# scHnRk_6.net
KiCad netlist of a schematic drawn in EAGLE
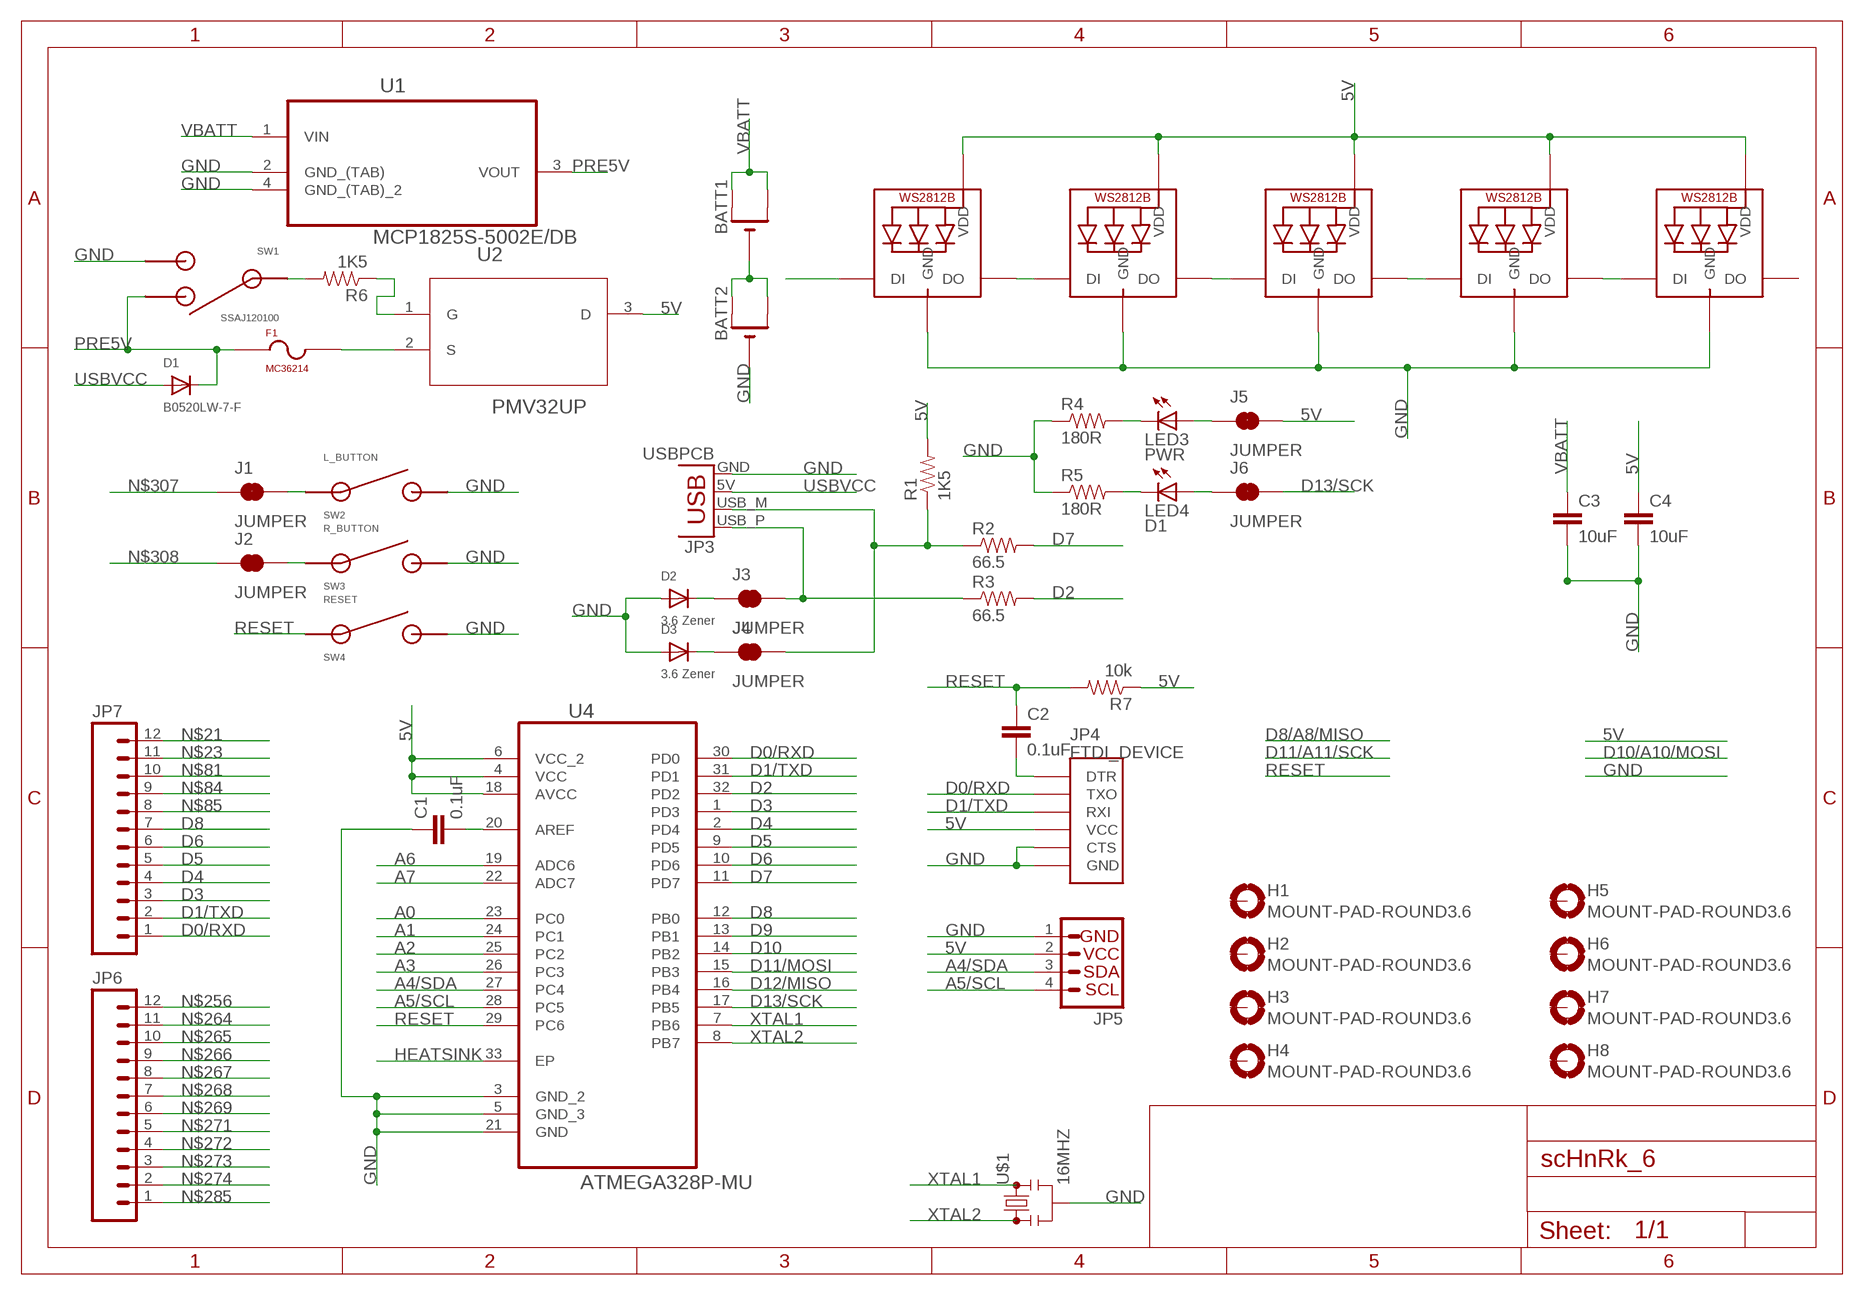
[diagram p0: schematic, sheet 1]

(export (version "E")
  (design (tool "Eeschema 10.0.6"))
  (components
    (comp (ref "BATT1")
      (value "CR2032SMT")
      (footprint "eagle-import:CR2032-SMD")
      (libsource (lib "eagle-import") (part "CR2032SMT"))
    )
    (comp (ref "BATT2")
      (value "CR2032SMT")
      (footprint "eagle-import:CR2032-SMD")
      (libsource (lib "eagle-import") (part "CR2032SMT"))
    )
    (comp (ref "C1")
      (value "0.1uF")
      (footprint "eagle-import:0805")
      (libsource (lib "eagle-import") (part "CAP0805"))
    )
    (comp (ref "C2")
      (value "0.1uF")
      (footprint "eagle-import:0805")
      (libsource (lib "eagle-import") (part "CAP0805"))
    )
    (comp (ref "C3")
      (value "10uF")
      (footprint "eagle-import:0805")
      (libsource (lib "eagle-import") (part "CAP0805"))
    )
    (comp (ref "C4")
      (value "10uF")
      (footprint "eagle-import:0805")
      (libsource (lib "eagle-import") (part "CAP0805"))
    )
    (comp (ref "D1")
      (value "B0520LW-7-F")
      (footprint "eagle-import:SOD-123")
      (libsource (lib "eagle-import") (part "DIODESOD-123"))
    )
    (comp (ref "D2")
      (value "3.6 Zener")
      (footprint "eagle-import:SOD-523")
      (libsource (lib "eagle-import") (part "DIODESOD-523"))
    )
    (comp (ref "D3")
      (value "3.6 Zener")
      (footprint "eagle-import:SOD-523")
      (libsource (lib "eagle-import") (part "DIODESOD-523"))
    )
    (comp (ref "F1")
      (value "MC36214")
      (footprint "eagle-import:MC36214")
      (libsource (lib "eagle-import") (part "MC36214"))
    )
    (comp (ref "H1")
      (value "MOUNT-PAD-ROUND3.6")
      (footprint "eagle-import:3,6-PAD")
      (libsource (lib "eagle-import") (part "MOUNT-PAD-ROUND3.6"))
    )
    (comp (ref "H2")
      (value "MOUNT-PAD-ROUND3.6")
      (footprint "eagle-import:3,6-PAD")
      (libsource (lib "eagle-import") (part "MOUNT-PAD-ROUND3.6"))
    )
    (comp (ref "H3")
      (value "MOUNT-PAD-ROUND3.6")
      (footprint "eagle-import:3,6-PAD")
      (libsource (lib "eagle-import") (part "MOUNT-PAD-ROUND3.6"))
    )
    (comp (ref "H4")
      (value "MOUNT-PAD-ROUND3.6")
      (footprint "eagle-import:3,6-PAD")
      (libsource (lib "eagle-import") (part "MOUNT-PAD-ROUND3.6"))
    )
    (comp (ref "H5")
      (value "MOUNT-PAD-ROUND3.6")
      (footprint "eagle-import:3,6-PAD")
      (libsource (lib "eagle-import") (part "MOUNT-PAD-ROUND3.6"))
    )
    (comp (ref "H6")
      (value "MOUNT-PAD-ROUND3.6")
      (footprint "eagle-import:3,6-PAD")
      (libsource (lib "eagle-import") (part "MOUNT-PAD-ROUND3.6"))
    )
    (comp (ref "H7")
      (value "MOUNT-PAD-ROUND3.6")
      (footprint "eagle-import:3,6-PAD")
      (libsource (lib "eagle-import") (part "MOUNT-PAD-ROUND3.6"))
    )
    (comp (ref "H8")
      (value "MOUNT-PAD-ROUND3.6")
      (footprint "eagle-import:3,6-PAD")
      (libsource (lib "eagle-import") (part "MOUNT-PAD-ROUND3.6"))
    )
    (comp (ref "J1")
      (value "JUMPER")
      (footprint "eagle-import:PAD-JUMPER-2-NC_BY_TRACE_YES_SILK")
      (libsource (lib "eagle-import") (part "JUMPER-PAD-2-NC_BY_TRACE"))
    )
    (comp (ref "J2")
      (value "JUMPER")
      (footprint "eagle-import:PAD-JUMPER-2-NC_BY_TRACE_YES_SILK")
      (libsource (lib "eagle-import") (part "JUMPER-PAD-2-NC_BY_TRACE"))
    )
    (comp (ref "J3")
      (value "JUMPER")
      (footprint "eagle-import:PAD-JUMPER-2-NC_BY_TRACE_YES_SILK")
      (libsource (lib "eagle-import") (part "JUMPER-PAD-2-NC_BY_TRACE"))
    )
    (comp (ref "J4")
      (value "JUMPER")
      (footprint "eagle-import:PAD-JUMPER-2-NC_BY_TRACE_YES_SILK")
      (libsource (lib "eagle-import") (part "JUMPER-PAD-2-NC_BY_TRACE"))
    )
    (comp (ref "J5")
      (value "JUMPER")
      (footprint "eagle-import:PAD-JUMPER-2-NC_BY_TRACE_YES_SILK")
      (libsource (lib "eagle-import") (part "JUMPER-PAD-2-NC_BY_TRACE"))
    )
    (comp (ref "J6")
      (value "JUMPER")
      (footprint "eagle-import:PAD-JUMPER-2-NC_BY_TRACE_YES_SILK")
      (libsource (lib "eagle-import") (part "JUMPER-PAD-2-NC_BY_TRACE"))
    )
    (comp (ref "JP3")
      (value "USBPCB")
      (footprint "eagle-import:USB-A-PCB")
      (libsource (lib "eagle-import") (part "USBPCB"))
    )
    (comp (ref "JP4")
      (value "FTDI_DEVICE")
      (footprint "eagle-import:FTDI_DEVICE_SIDE")
      (libsource (lib "eagle-import") (part "FTDI_DEVICE"))
    )
    (comp (ref "JP5")
      (value "I2C_STANDARD")
      (footprint "eagle-import:1X04")
      (libsource (lib "eagle-import") (part "I2C_STANDARD"))
    )
    (comp (ref "JP6")
      (value "M12PTH")
      (footprint "eagle-import:1X12")
      (libsource (lib "eagle-import") (part "M12PTH"))
    )
    (comp (ref "JP7")
      (value "M12PTH")
      (footprint "eagle-import:1X12")
      (libsource (lib "eagle-import") (part "M12PTH"))
    )
    (comp (ref "LED1")
      (value "WS2812B5050")
      (footprint "eagle-import:WS2812B")
      (libsource (lib "eagle-import") (part "WS2812B5050"))
    )
    (comp (ref "LED2")
      (value "WS2812B5050")
      (footprint "eagle-import:WS2812B")
      (libsource (lib "eagle-import") (part "WS2812B5050"))
    )
    (comp (ref "LED3")
      (value "PWR")
      (footprint "eagle-import:CHIPLED_0603")
      (libsource (lib "eagle-import") (part "LEDCHIPLED_0603"))
    )
    (comp (ref "LED4")
      (value "D1")
      (footprint "eagle-import:CHIPLED_0603")
      (libsource (lib "eagle-import") (part "LEDCHIPLED_0603"))
    )
    (comp (ref "LED5")
      (value "WS2812B5050")
      (footprint "eagle-import:WS2812B")
      (libsource (lib "eagle-import") (part "WS2812B5050"))
    )
    (comp (ref "LED6")
      (value "WS2812B5050")
      (footprint "eagle-import:WS2812B")
      (libsource (lib "eagle-import") (part "WS2812B5050"))
    )
    (comp (ref "LED7")
      (value "WS2812B5050")
      (footprint "eagle-import:WS2812B")
      (libsource (lib "eagle-import") (part "WS2812B5050"))
    )
    (comp (ref "R1")
      (value "1K5")
      (footprint "eagle-import:0805")
      (libsource (lib "eagle-import") (part "RESISTOR0805-RES"))
    )
    (comp (ref "R2")
      (value "66.5")
      (footprint "eagle-import:0603-RES")
      (libsource (lib "eagle-import") (part "RESISTOR0603-RES"))
    )
    (comp (ref "R3")
      (value "66.5")
      (footprint "eagle-import:0603-RES")
      (libsource (lib "eagle-import") (part "RESISTOR0603-RES"))
    )
    (comp (ref "R4")
      (value "180R")
      (footprint "eagle-import:0805")
      (libsource (lib "eagle-import") (part "RESISTOR0805-RES"))
    )
    (comp (ref "R5")
      (value "180R")
      (footprint "eagle-import:0805")
      (libsource (lib "eagle-import") (part "RESISTOR0805-RES"))
    )
    (comp (ref "R6")
      (value "1K5")
      (footprint "eagle-import:0805")
      (libsource (lib "eagle-import") (part "RESISTOR0805-RES"))
    )
    (comp (ref "R7")
      (value "10k")
      (footprint "eagle-import:0805")
      (libsource (lib "eagle-import") (part "RESISTOR0805-RES"))
    )
    (comp (ref "SW1")
      (value "SSAJ120100")
      (footprint "eagle-import:SSAJ120100")
      (libsource (lib "eagle-import") (part "SSAJ120100"))
    )
    (comp (ref "SW2")
      (value "L_BUTTON")
      (footprint "eagle-import:SKRBAGE010")
      (libsource (lib "eagle-import") (part "SKRBAGE010"))
    )
    (comp (ref "SW3")
      (value "R_BUTTON")
      (footprint "eagle-import:SKRBAGE010")
      (libsource (lib "eagle-import") (part "SKRBAGE010"))
    )
    (comp (ref "SW4")
      (value "RESET")
      (footprint "eagle-import:SKRBAGE010")
      (libsource (lib "eagle-import") (part "SKRBAGE010"))
    )
    (comp (ref "U$1")
      (value "16MHZ")
      (footprint "eagle-import:RESONATOR-SMD")
      (libsource (lib "eagle-import") (part "RESONATOR16MHZ"))
    )
    (comp (ref "U1")
      (value "MCP1825S-5002E/DB")
      (footprint "eagle-import:SOT230P700X180-4N")
      (libsource (lib "eagle-import") (part "MCP1825S-5002E/DB"))
    )
    (comp (ref "U2")
      (value "PMV32UP")
      (footprint "eagle-import:SOT95P230X110-3N")
      (libsource (lib "eagle-import") (part "PMV32UP"))
    )
    (comp (ref "U4")
      (value "ATMEGA328P-MU")
      (footprint "eagle-import:QFN50P500X500X100-33N")
      (libsource (lib "eagle-import") (part "ATMEGA328P-MU"))
    )
  )
  (nets
    (net (code "1") (name "/5V") (class "Default")
      (node (ref "C4") (pin "1") (pinfunction "1_1") (pintype "passive"))
      (node (ref "J5") (pin "2") (pinfunction "2_2") (pintype "passive"))
      (node (ref "JP4") (pin "P$4") (pinfunction "VCC_P$4") (pintype "bidirectional"))
      (node (ref "JP5") (pin "2") (pinfunction "2_2") (pintype "passive"))
      (node (ref "LED1") (pin "1-VDD") (pinfunction "VDD_1-VDD") (pintype "power_in"))
      (node (ref "LED2") (pin "1-VDD") (pinfunction "VDD_1-VDD") (pintype "power_in"))
      (node (ref "LED5") (pin "1-VDD") (pinfunction "VDD_1-VDD") (pintype "power_in"))
      (node (ref "LED6") (pin "1-VDD") (pinfunction "VDD_1-VDD") (pintype "power_in"))
      (node (ref "LED7") (pin "1-VDD") (pinfunction "VDD_1-VDD") (pintype "power_in"))
      (node (ref "R1") (pin "2") (pinfunction "2_2") (pintype "passive"))
      (node (ref "R7") (pin "1") (pinfunction "1_1") (pintype "passive"))
      (node (ref "U2") (pin "3") (pinfunction "D_3") (pintype "passive"))
      (node (ref "U4") (pin "18") (pinfunction "AVCC_18") (pintype "power_in"))
      (node (ref "U4") (pin "4") (pinfunction "VCC_4") (pintype "power_in"))
      (node (ref "U4") (pin "6") (pinfunction "VCC_2_6") (pintype "power_in"))
    )
    (net (code "2") (name "/A0") (class "Default")
      (node (ref "U4") (pin "23") (pinfunction "PC0_23") (pintype "bidirectional"))
    )
    (net (code "3") (name "/A1") (class "Default")
      (node (ref "U4") (pin "24") (pinfunction "PC1_24") (pintype "bidirectional"))
    )
    (net (code "4") (name "/A2") (class "Default")
      (node (ref "U4") (pin "25") (pinfunction "PC2_25") (pintype "bidirectional"))
    )
    (net (code "5") (name "/A3") (class "Default")
      (node (ref "U4") (pin "26") (pinfunction "PC3_26") (pintype "bidirectional"))
    )
    (net (code "6") (name "/A4{slash}SDA") (class "Default")
      (node (ref "JP5") (pin "3") (pinfunction "3_3") (pintype "passive"))
      (node (ref "U4") (pin "27") (pinfunction "PC4_27") (pintype "bidirectional"))
    )
    (net (code "7") (name "/A5{slash}SCL") (class "Default")
      (node (ref "JP5") (pin "4") (pinfunction "4_4") (pintype "passive"))
      (node (ref "U4") (pin "28") (pinfunction "PC5_28") (pintype "bidirectional"))
    )
    (net (code "8") (name "/A6") (class "Default")
      (node (ref "U4") (pin "19") (pinfunction "ADC6_19") (pintype "input"))
    )
    (net (code "9") (name "/A7") (class "Default")
      (node (ref "U4") (pin "22") (pinfunction "ADC7_22") (pintype "input"))
    )
    (net (code "10") (name "/D0{slash}RXD") (class "Default")
      (node (ref "JP4") (pin "P$2") (pinfunction "TXO_P$2") (pintype "bidirectional"))
      (node (ref "JP7") (pin "1") (pinfunction "1_1") (pintype "passive"))
      (node (ref "U4") (pin "30") (pinfunction "PD0_30") (pintype "bidirectional"))
    )
    (net (code "11") (name "/D1{slash}TXD") (class "Default")
      (node (ref "JP4") (pin "P$3") (pinfunction "RXI_P$3") (pintype "bidirectional"))
      (node (ref "JP7") (pin "2") (pinfunction "2_2") (pintype "passive"))
      (node (ref "U4") (pin "31") (pinfunction "PD1_31") (pintype "bidirectional"))
    )
    (net (code "12") (name "/D2") (class "Default")
      (node (ref "R3") (pin "2") (pinfunction "2_2") (pintype "passive"))
      (node (ref "U4") (pin "32") (pinfunction "PD2_32") (pintype "bidirectional"))
    )
    (net (code "13") (name "/D3") (class "Default")
      (node (ref "JP7") (pin "3") (pinfunction "3_3") (pintype "passive"))
      (node (ref "U4") (pin "1") (pinfunction "PD3_1") (pintype "bidirectional"))
    )
    (net (code "14") (name "/D4") (class "Default")
      (node (ref "JP7") (pin "4") (pinfunction "4_4") (pintype "passive"))
      (node (ref "U4") (pin "2") (pinfunction "PD4_2") (pintype "bidirectional"))
    )
    (net (code "15") (name "/D5") (class "Default")
      (node (ref "JP7") (pin "5") (pinfunction "5_5") (pintype "passive"))
      (node (ref "U4") (pin "9") (pinfunction "PD5_9") (pintype "bidirectional"))
    )
    (net (code "16") (name "/D6") (class "Default")
      (node (ref "JP7") (pin "6") (pinfunction "6_6") (pintype "passive"))
      (node (ref "U4") (pin "10") (pinfunction "PD6_10") (pintype "bidirectional"))
    )
    (net (code "17") (name "/D7") (class "Default")
      (node (ref "R2") (pin "2") (pinfunction "2_2") (pintype "passive"))
      (node (ref "U4") (pin "11") (pinfunction "PD7_11") (pintype "bidirectional"))
    )
    (net (code "18") (name "/D8") (class "Default")
      (node (ref "JP7") (pin "7") (pinfunction "7_7") (pintype "passive"))
      (node (ref "U4") (pin "12") (pinfunction "PB0_12") (pintype "bidirectional"))
    )
    (net (code "20") (name "/D9") (class "Default")
      (node (ref "U4") (pin "13") (pinfunction "PB1_13") (pintype "bidirectional"))
    )
    (net (code "21") (name "/D10") (class "Default")
      (node (ref "U4") (pin "14") (pinfunction "PB2_14") (pintype "bidirectional"))
    )
    (net (code "24") (name "/D11{slash}MOSI") (class "Default")
      (node (ref "U4") (pin "15") (pinfunction "PB3_15") (pintype "bidirectional"))
    )
    (net (code "25") (name "/D12{slash}MISO") (class "Default")
      (node (ref "U4") (pin "16") (pinfunction "PB4_16") (pintype "bidirectional"))
    )
    (net (code "26") (name "/D13{slash}SCK") (class "Default")
      (node (ref "J6") (pin "2") (pinfunction "2_2") (pintype "passive"))
      (node (ref "U4") (pin "17") (pinfunction "PB5_17") (pintype "bidirectional"))
    )
    (net (code "27") (name "/GND") (class "Default")
      (node (ref "BATT2") (pin "-") (pinfunction "-_-") (pintype "passive"))
      (node (ref "C1") (pin "1") (pinfunction "1_1") (pintype "passive"))
      (node (ref "C3") (pin "2") (pinfunction "2_2") (pintype "passive"))
      (node (ref "C4") (pin "2") (pinfunction "2_2") (pintype "passive"))
      (node (ref "D2") (pin "A") (pinfunction "A_A") (pintype "passive"))
      (node (ref "D3") (pin "A") (pinfunction "A_A") (pintype "passive"))
      (node (ref "JP3") (pin "GND") (pinfunction "GND_GND") (pintype "bidirectional"))
      (node (ref "JP4") (pin "P$5") (pinfunction "CTS_P$5") (pintype "bidirectional"))
      (node (ref "JP4") (pin "P$6") (pinfunction "GND_P$6") (pintype "bidirectional"))
      (node (ref "JP5") (pin "1") (pinfunction "1_1") (pintype "passive"))
      (node (ref "LED1") (pin "3-GND") (pinfunction "GND_3-GND") (pintype "power_in"))
      (node (ref "LED2") (pin "3-GND") (pinfunction "GND_3-GND") (pintype "power_in"))
      (node (ref "LED5") (pin "3-GND") (pinfunction "GND_3-GND") (pintype "power_in"))
      (node (ref "LED6") (pin "3-GND") (pinfunction "GND_3-GND") (pintype "power_in"))
      (node (ref "LED7") (pin "3-GND") (pinfunction "GND_3-GND") (pintype "power_in"))
      (node (ref "R4") (pin "1") (pinfunction "1_1") (pintype "passive"))
      (node (ref "R5") (pin "1") (pinfunction "1_1") (pintype "passive"))
      (node (ref "SW1") (pin "P$2") (pinfunction "P$2_P$2") (pintype "bidirectional"))
      (node (ref "SW2") (pin "P$2") (pinfunction "P$2_P$2") (pintype "bidirectional"))
      (node (ref "SW2") (pin "P$4") (pinfunction "P$2_P$4") (pintype "bidirectional"))
      (node (ref "SW3") (pin "P$2") (pinfunction "P$2_P$2") (pintype "bidirectional"))
      (node (ref "SW3") (pin "P$4") (pinfunction "P$2_P$4") (pintype "bidirectional"))
      (node (ref "SW4") (pin "P$2") (pinfunction "P$2_P$2") (pintype "bidirectional"))
      (node (ref "SW4") (pin "P$4") (pinfunction "P$2_P$4") (pintype "bidirectional"))
      (node (ref "U$1") (pin "2") (pinfunction "2_2") (pintype "passive"))
      (node (ref "U1") (pin "2") (pinfunction "GND_(TAB)_2") (pintype "passive"))
      (node (ref "U1") (pin "4") (pinfunction "GND_(TAB)_2_4") (pintype "passive"))
      (node (ref "U4") (pin "21") (pinfunction "GND_21") (pintype "passive"))
      (node (ref "U4") (pin "3") (pinfunction "GND_2_3") (pintype "passive"))
      (node (ref "U4") (pin "5") (pinfunction "GND_3_5") (pintype "passive"))
    )
    (net (code "28") (name "/HEATSINK") (class "Default")
      (node (ref "U4") (pin "33") (pinfunction "EP_33") (pintype "passive"))
    )
    (net (code "29") (name "/N$21") (class "Default")
      (node (ref "JP7") (pin "12") (pinfunction "12_12") (pintype "passive"))
    )
    (net (code "30") (name "/N$23") (class "Default")
      (node (ref "JP7") (pin "11") (pinfunction "11_11") (pintype "passive"))
    )
    (net (code "31") (name "/N$81") (class "Default")
      (node (ref "JP7") (pin "10") (pinfunction "10_10") (pintype "passive"))
    )
    (net (code "32") (name "/N$84") (class "Default")
      (node (ref "JP7") (pin "9") (pinfunction "9_9") (pintype "passive"))
    )
    (net (code "33") (name "/N$85") (class "Default")
      (node (ref "JP7") (pin "8") (pinfunction "8_8") (pintype "passive"))
    )
    (net (code "34") (name "/N$256") (class "Default")
      (node (ref "JP6") (pin "12") (pinfunction "12_12") (pintype "passive"))
    )
    (net (code "35") (name "/N$264") (class "Default")
      (node (ref "JP6") (pin "11") (pinfunction "11_11") (pintype "passive"))
    )
    (net (code "36") (name "/N$265") (class "Default")
      (node (ref "JP6") (pin "10") (pinfunction "10_10") (pintype "passive"))
    )
    (net (code "37") (name "/N$266") (class "Default")
      (node (ref "JP6") (pin "9") (pinfunction "9_9") (pintype "passive"))
    )
    (net (code "38") (name "/N$267") (class "Default")
      (node (ref "JP6") (pin "8") (pinfunction "8_8") (pintype "passive"))
    )
    (net (code "39") (name "/N$268") (class "Default")
      (node (ref "JP6") (pin "7") (pinfunction "7_7") (pintype "passive"))
    )
    (net (code "40") (name "/N$269") (class "Default")
      (node (ref "JP6") (pin "6") (pinfunction "6_6") (pintype "passive"))
    )
    (net (code "41") (name "/N$271") (class "Default")
      (node (ref "JP6") (pin "5") (pinfunction "5_5") (pintype "passive"))
    )
    (net (code "42") (name "/N$272") (class "Default")
      (node (ref "JP6") (pin "4") (pinfunction "4_4") (pintype "passive"))
    )
    (net (code "43") (name "/N$273") (class "Default")
      (node (ref "JP6") (pin "3") (pinfunction "3_3") (pintype "passive"))
    )
    (net (code "44") (name "/N$274") (class "Default")
      (node (ref "JP6") (pin "2") (pinfunction "2_2") (pintype "passive"))
    )
    (net (code "45") (name "/N$285") (class "Default")
      (node (ref "JP6") (pin "1") (pinfunction "1_1") (pintype "passive"))
    )
    (net (code "46") (name "/N$307") (class "Default")
      (node (ref "J1") (pin "1") (pinfunction "1_1") (pintype "passive"))
    )
    (net (code "47") (name "/N$308") (class "Default")
      (node (ref "J2") (pin "1") (pinfunction "1_1") (pintype "passive"))
    )
    (net (code "48") (name "/PRE5V") (class "Default")
      (node (ref "D1") (pin "C") (pinfunction "C_C") (pintype "passive"))
      (node (ref "F1") (pin "P$1") (pinfunction "P$1_P$1") (pintype "bidirectional"))
      (node (ref "SW1") (pin "P$1") (pinfunction "P$1_P$1") (pintype "bidirectional"))
      (node (ref "U1") (pin "3") (pinfunction "VOUT_3") (pintype "output"))
    )
    (net (code "49") (name "/RESET") (class "Default")
      (node (ref "C2") (pin "1") (pinfunction "1_1") (pintype "passive"))
      (node (ref "R7") (pin "2") (pinfunction "2_2") (pintype "passive"))
      (node (ref "SW4") (pin "P$1") (pinfunction "P$1_P$1") (pintype "bidirectional"))
      (node (ref "SW4") (pin "P$3") (pinfunction "P$1_P$3") (pintype "bidirectional"))
      (node (ref "U4") (pin "29") (pinfunction "PC6_29") (pintype "bidirectional"))
    )
    (net (code "50") (name "/USBVCC") (class "Default")
      (node (ref "D1") (pin "A") (pinfunction "A_A") (pintype "passive"))
      (node (ref "JP3") (pin "5V") (pinfunction "VBUS_5V") (pintype "bidirectional"))
    )
    (net (code "51") (name "/VBATT") (class "Default")
      (node (ref "BATT1") (pin "+$1") (pinfunction "+_+$1") (pintype "passive"))
      (node (ref "BATT1") (pin "+$2") (pinfunction "+1_+$2") (pintype "passive"))
      (node (ref "C3") (pin "1") (pinfunction "1_1") (pintype "passive"))
      (node (ref "U1") (pin "1") (pinfunction "VIN_1") (pintype "input"))
    )
    (net (code "52") (name "/XTAL1") (class "Default")
      (node (ref "U$1") (pin "3") (pinfunction "3_3") (pintype "passive"))
      (node (ref "U4") (pin "7") (pinfunction "PB6_7") (pintype "bidirectional"))
    )
    (net (code "53") (name "/XTAL2") (class "Default")
      (node (ref "U$1") (pin "1") (pinfunction "1_1") (pintype "passive"))
      (node (ref "U4") (pin "8") (pinfunction "PB7_8") (pintype "bidirectional"))
    )
    (net (code "54") (name "Net-(BATT2-+)") (class "Default")
      (node (ref "BATT1") (pin "-") (pinfunction "-_-") (pintype "passive"))
      (node (ref "BATT2") (pin "+$1") (pinfunction "+_+$1") (pintype "passive"))
      (node (ref "BATT2") (pin "+$2") (pinfunction "+1_+$2") (pintype "passive"))
    )
    (net (code "55") (name "Net-(D2-C)") (class "Default")
      (node (ref "D2") (pin "K") (pinfunction "C_K") (pintype "passive"))
      (node (ref "J3") (pin "1") (pinfunction "1_1") (pintype "passive"))
    )
    (net (code "56") (name "Net-(D3-C)") (class "Default")
      (node (ref "D3") (pin "K") (pinfunction "C_K") (pintype "passive"))
      (node (ref "J4") (pin "1") (pinfunction "1_1") (pintype "passive"))
    )
    (net (code "57") (name "Net-(J1-Pad2)") (class "Default")
      (node (ref "J1") (pin "2") (pinfunction "2_2") (pintype "passive"))
      (node (ref "SW2") (pin "P$1") (pinfunction "P$1_P$1") (pintype "bidirectional"))
      (node (ref "SW2") (pin "P$3") (pinfunction "P$1_P$3") (pintype "bidirectional"))
    )
    (net (code "58") (name "Net-(J2-Pad2)") (class "Default")
      (node (ref "J2") (pin "2") (pinfunction "2_2") (pintype "passive"))
      (node (ref "SW3") (pin "P$1") (pinfunction "P$1_P$1") (pintype "bidirectional"))
      (node (ref "SW3") (pin "P$3") (pinfunction "P$1_P$3") (pintype "bidirectional"))
    )
    (net (code "59") (name "Net-(J5-Pad1)") (class "Default")
      (node (ref "J5") (pin "1") (pinfunction "1_1") (pintype "passive"))
      (node (ref "LED3") (pin "A") (pinfunction "A_A") (pintype "passive"))
    )
    (net (code "60") (name "Net-(J6-Pad1)") (class "Default")
      (node (ref "J6") (pin "1") (pinfunction "1_1") (pintype "passive"))
      (node (ref "LED4") (pin "A") (pinfunction "A_A") (pintype "passive"))
    )
    (net (code "61") (name "Net-(JP3-D+)") (class "Default")
      (node (ref "J3") (pin "2") (pinfunction "2_2") (pintype "passive"))
      (node (ref "JP3") (pin "USB_P") (pinfunction "D+_USB_P") (pintype "bidirectional"))
      (node (ref "R3") (pin "1") (pinfunction "1_1") (pintype "passive"))
    )
    (net (code "62") (name "Net-(JP3-D-)") (class "Default")
      (node (ref "J4") (pin "2") (pinfunction "2_2") (pintype "passive"))
      (node (ref "JP3") (pin "USB_M") (pinfunction "D-_USB_M") (pintype "bidirectional"))
      (node (ref "R1") (pin "1") (pinfunction "1_1") (pintype "passive"))
      (node (ref "R2") (pin "1") (pinfunction "1_1") (pintype "passive"))
    )
    (net (code "63") (name "Net-(JP4-DTR)") (class "Default")
      (node (ref "C2") (pin "2") (pinfunction "2_2") (pintype "passive"))
      (node (ref "JP4") (pin "P$1") (pinfunction "DTR_P$1") (pintype "bidirectional"))
    )
    (net (code "64") (name "Net-(LED1-DO)") (class "Default")
      (node (ref "LED1") (pin "2-DOUT") (pinfunction "DO_2-DOUT") (pintype "output"))
      (node (ref "LED2") (pin "4-DIN") (pinfunction "DI_4-DIN") (pintype "input"))
    )
    (net (code "65") (name "Net-(LED2-DO)") (class "Default")
      (node (ref "LED2") (pin "2-DOUT") (pinfunction "DO_2-DOUT") (pintype "output"))
      (node (ref "LED5") (pin "4-DIN") (pinfunction "DI_4-DIN") (pintype "input"))
    )
    (net (code "66") (name "Net-(LED3-PadC)") (class "Default")
      (node (ref "LED3") (pin "C") (pinfunction "C_C") (pintype "passive"))
      (node (ref "R4") (pin "2") (pinfunction "2_2") (pintype "passive"))
    )
    (net (code "67") (name "Net-(LED4-PadC)") (class "Default")
      (node (ref "LED4") (pin "C") (pinfunction "C_C") (pintype "passive"))
      (node (ref "R5") (pin "2") (pinfunction "2_2") (pintype "passive"))
    )
    (net (code "68") (name "Net-(LED5-DO)") (class "Default")
      (node (ref "LED5") (pin "2-DOUT") (pinfunction "DO_2-DOUT") (pintype "output"))
      (node (ref "LED6") (pin "4-DIN") (pinfunction "DI_4-DIN") (pintype "input"))
    )
    (net (code "69") (name "Net-(LED6-DO)") (class "Default")
      (node (ref "LED6") (pin "2-DOUT") (pinfunction "DO_2-DOUT") (pintype "output"))
      (node (ref "LED7") (pin "4-DIN") (pinfunction "DI_4-DIN") (pintype "input"))
    )
    (net (code "70") (name "Net-(R6-Pad2)") (class "Default")
      (node (ref "R6") (pin "2") (pinfunction "2_2") (pintype "passive"))
      (node (ref "SW1") (pin "P$C") (pinfunction "P$C_P$C") (pintype "bidirectional"))
    )
    (net (code "71") (name "Net-(U2-G)") (class "Default")
      (node (ref "R6") (pin "1") (pinfunction "1_1") (pintype "passive"))
      (node (ref "U2") (pin "1") (pinfunction "G_1") (pintype "passive"))
    )
    (net (code "72") (name "Net-(U2-S)") (class "Default")
      (node (ref "F1") (pin "P$2") (pinfunction "P$2_P$2") (pintype "bidirectional"))
      (node (ref "U2") (pin "2") (pinfunction "S_2") (pintype "passive"))
    )
    (net (code "73") (name "Net-(U4-AREF)") (class "Default")
      (node (ref "C1") (pin "2") (pinfunction "2_2") (pintype "passive"))
      (node (ref "U4") (pin "20") (pinfunction "AREF_20") (pintype "input"))
    )
    (net (code "74") (name "unconnected-(H1-MOUNT-PadB3,6)") (class "Default")
      (node (ref "H1") (pin "B3,6") (pinfunction "MOUNT_B3,6") (pintype "passive"))
    )
    (net (code "75") (name "unconnected-(H2-MOUNT-PadB3,6)") (class "Default")
      (node (ref "H2") (pin "B3,6") (pinfunction "MOUNT_B3,6") (pintype "passive"))
    )
    (net (code "76") (name "unconnected-(H3-MOUNT-PadB3,6)") (class "Default")
      (node (ref "H3") (pin "B3,6") (pinfunction "MOUNT_B3,6") (pintype "passive"))
    )
    (net (code "77") (name "unconnected-(H4-MOUNT-PadB3,6)") (class "Default")
      (node (ref "H4") (pin "B3,6") (pinfunction "MOUNT_B3,6") (pintype "passive"))
    )
    (net (code "78") (name "unconnected-(H5-MOUNT-PadB3,6)") (class "Default")
      (node (ref "H5") (pin "B3,6") (pinfunction "MOUNT_B3,6") (pintype "passive"))
    )
    (net (code "79") (name "unconnected-(H6-MOUNT-PadB3,6)") (class "Default")
      (node (ref "H6") (pin "B3,6") (pinfunction "MOUNT_B3,6") (pintype "passive"))
    )
    (net (code "80") (name "unconnected-(H7-MOUNT-PadB3,6)") (class "Default")
      (node (ref "H7") (pin "B3,6") (pinfunction "MOUNT_B3,6") (pintype "passive"))
    )
    (net (code "81") (name "unconnected-(H8-MOUNT-PadB3,6)") (class "Default")
      (node (ref "H8") (pin "B3,6") (pinfunction "MOUNT_B3,6") (pintype "passive"))
    )
    (net (code "82") (name "unconnected-(LED1-DI-Pad4-DIN)") (class "Default")
      (node (ref "LED1") (pin "4-DIN") (pinfunction "DI_4-DIN") (pintype "input"))
    )
    (net (code "83") (name "unconnected-(LED7-DO-Pad2-DOUT)") (class "Default")
      (node (ref "LED7") (pin "2-DOUT") (pinfunction "DO_2-DOUT") (pintype "output"))
    )
  )
)
